# 2te8LED_v04.net
KiCad netlist of a schematic drawn in EAGLE
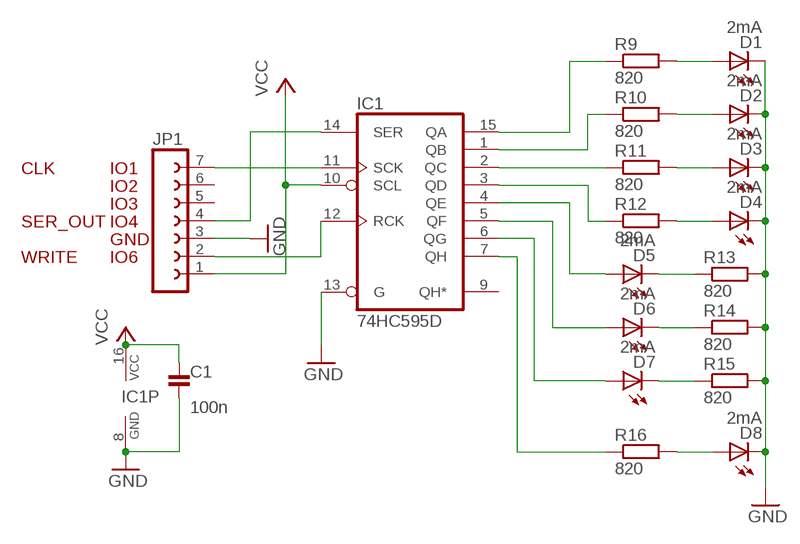
[diagram p0: schematic, sheet 1]

(export (version "E")
  (design (tool "Eeschema 10.0.6"))
  (components
    (comp (ref "C1")
      (value "100n")
      (footprint "eagle-import:C0805")
      (libsource (lib "eagle-import") (part "C-EUC0805"))
    )
    (comp (ref "D1")
      (value "2mA")
      (footprint "eagle-import:LED3MM")
      (libsource (lib "eagle-import") (part "LED3MM"))
    )
    (comp (ref "D2")
      (value "2mA")
      (footprint "eagle-import:LED3MM")
      (libsource (lib "eagle-import") (part "LED3MM"))
    )
    (comp (ref "D3")
      (value "2mA")
      (footprint "eagle-import:LED3MM")
      (libsource (lib "eagle-import") (part "LED3MM"))
    )
    (comp (ref "D4")
      (value "2mA")
      (footprint "eagle-import:LED3MM")
      (libsource (lib "eagle-import") (part "LED3MM"))
    )
    (comp (ref "D5")
      (value "2mA")
      (footprint "eagle-import:LED3MM")
      (libsource (lib "eagle-import") (part "LED3MM"))
    )
    (comp (ref "D6")
      (value "2mA")
      (footprint "eagle-import:LED3MM")
      (libsource (lib "eagle-import") (part "LED3MM"))
    )
    (comp (ref "D7")
      (value "2mA")
      (footprint "eagle-import:LED3MM")
      (libsource (lib "eagle-import") (part "LED3MM"))
    )
    (comp (ref "D8")
      (value "2mA")
      (footprint "eagle-import:LED3MM")
      (libsource (lib "eagle-import") (part "LED3MM"))
    )
    (comp (ref "IC1")
      (value "74HC595D")
      (footprint "eagle-import:SO16")
      (libsource (lib "eagle-import") (part "74595DHC"))
    )
    (comp (ref "JP1")
      (value "FE07-1")
      (footprint "eagle-import:FE07")
      (libsource (lib "eagle-import") (part "FE07-1"))
    )
    (comp (ref "R9")
      (value "820")
      (footprint "eagle-import:R0805")
      (libsource (lib "eagle-import") (part "R-EU_R0805"))
    )
    (comp (ref "R10")
      (value "820")
      (footprint "eagle-import:R0805")
      (libsource (lib "eagle-import") (part "R-EU_R0805"))
    )
    (comp (ref "R11")
      (value "820")
      (footprint "eagle-import:R0805")
      (libsource (lib "eagle-import") (part "R-EU_R0805"))
    )
    (comp (ref "R12")
      (value "820")
      (footprint "eagle-import:R0805")
      (libsource (lib "eagle-import") (part "R-EU_R0805"))
    )
    (comp (ref "R13")
      (value "820")
      (footprint "eagle-import:R0805")
      (libsource (lib "eagle-import") (part "R-EU_R0805"))
    )
    (comp (ref "R14")
      (value "820")
      (footprint "eagle-import:R0805")
      (libsource (lib "eagle-import") (part "R-EU_R0805"))
    )
    (comp (ref "R15")
      (value "820")
      (footprint "eagle-import:R0805")
      (libsource (lib "eagle-import") (part "R-EU_R0805"))
    )
    (comp (ref "R16")
      (value "820")
      (footprint "eagle-import:R0805")
      (libsource (lib "eagle-import") (part "R-EU_R0805"))
    )
  )
  (nets
    (net (code "1") (name "GND") (class "Default")
      (node (ref "C1") (pin "2") (pinfunction "2_2") (pintype "passive"))
      (node (ref "D1") (pin "K") (pinfunction "C_K") (pintype "passive"))
      (node (ref "D2") (pin "K") (pinfunction "C_K") (pintype "passive"))
      (node (ref "D3") (pin "K") (pinfunction "C_K") (pintype "passive"))
      (node (ref "D4") (pin "K") (pinfunction "C_K") (pintype "passive"))
      (node (ref "D8") (pin "K") (pinfunction "C_K") (pintype "passive"))
      (node (ref "IC1") (pin "13") (pinfunction "G_13") (pintype "input"))
      (node (ref "IC1") (pin "8") (pinfunction "GND_8") (pintype "power_in"))
      (node (ref "JP1") (pin "3") (pinfunction "3_3") (pintype "passive"))
      (node (ref "R13") (pin "2") (pinfunction "2_2") (pintype "passive"))
      (node (ref "R14") (pin "2") (pinfunction "2_2") (pintype "passive"))
      (node (ref "R15") (pin "2") (pinfunction "2_2") (pintype "passive"))
    )
    (net (code "2") (name "Net-(D1-PadA)") (class "Default")
      (node (ref "D1") (pin "A") (pinfunction "A_A") (pintype "passive"))
      (node (ref "R9") (pin "2") (pinfunction "2_2") (pintype "passive"))
    )
    (net (code "3") (name "Net-(D2-PadA)") (class "Default")
      (node (ref "D2") (pin "A") (pinfunction "A_A") (pintype "passive"))
      (node (ref "R10") (pin "2") (pinfunction "2_2") (pintype "passive"))
    )
    (net (code "4") (name "Net-(D3-PadA)") (class "Default")
      (node (ref "D3") (pin "A") (pinfunction "A_A") (pintype "passive"))
      (node (ref "R11") (pin "2") (pinfunction "2_2") (pintype "passive"))
    )
    (net (code "5") (name "Net-(D4-PadA)") (class "Default")
      (node (ref "D4") (pin "A") (pinfunction "A_A") (pintype "passive"))
      (node (ref "R12") (pin "2") (pinfunction "2_2") (pintype "passive"))
    )
    (net (code "6") (name "Net-(D5-C)") (class "Default")
      (node (ref "D5") (pin "K") (pinfunction "C_K") (pintype "passive"))
      (node (ref "R13") (pin "1") (pinfunction "1_1") (pintype "passive"))
    )
    (net (code "7") (name "Net-(D6-C)") (class "Default")
      (node (ref "D6") (pin "K") (pinfunction "C_K") (pintype "passive"))
      (node (ref "R14") (pin "1") (pinfunction "1_1") (pintype "passive"))
    )
    (net (code "8") (name "Net-(D7-C)") (class "Default")
      (node (ref "D7") (pin "K") (pinfunction "C_K") (pintype "passive"))
      (node (ref "R15") (pin "1") (pinfunction "1_1") (pintype "passive"))
    )
    (net (code "9") (name "Net-(D8-PadA)") (class "Default")
      (node (ref "D8") (pin "A") (pinfunction "A_A") (pintype "passive"))
      (node (ref "R16") (pin "2") (pinfunction "2_2") (pintype "passive"))
    )
    (net (code "10") (name "Net-(IC1A-QA)") (class "Default")
      (node (ref "IC1") (pin "15") (pinfunction "QA_15") (pintype "tri_state"))
      (node (ref "R9") (pin "1") (pinfunction "1_1") (pintype "passive"))
    )
    (net (code "11") (name "Net-(IC1A-QB)") (class "Default")
      (node (ref "IC1") (pin "1") (pinfunction "QB_1") (pintype "tri_state"))
      (node (ref "R10") (pin "1") (pinfunction "1_1") (pintype "passive"))
    )
    (net (code "12") (name "Net-(IC1A-QC)") (class "Default")
      (node (ref "IC1") (pin "2") (pinfunction "QC_2") (pintype "tri_state"))
      (node (ref "R11") (pin "1") (pinfunction "1_1") (pintype "passive"))
    )
    (net (code "13") (name "Net-(IC1A-QD)") (class "Default")
      (node (ref "IC1") (pin "3") (pinfunction "QD_3") (pintype "tri_state"))
      (node (ref "R12") (pin "1") (pinfunction "1_1") (pintype "passive"))
    )
    (net (code "14") (name "Net-(IC1A-QE)") (class "Default")
      (node (ref "D5") (pin "A") (pinfunction "A_A") (pintype "passive"))
      (node (ref "IC1") (pin "4") (pinfunction "QE_4") (pintype "tri_state"))
    )
    (net (code "15") (name "Net-(IC1A-QF)") (class "Default")
      (node (ref "D6") (pin "A") (pinfunction "A_A") (pintype "passive"))
      (node (ref "IC1") (pin "5") (pinfunction "QF_5") (pintype "tri_state"))
    )
    (net (code "16") (name "Net-(IC1A-QG)") (class "Default")
      (node (ref "D7") (pin "A") (pinfunction "A_A") (pintype "passive"))
      (node (ref "IC1") (pin "6") (pinfunction "QG_6") (pintype "tri_state"))
    )
    (net (code "17") (name "Net-(IC1A-QH)") (class "Default")
      (node (ref "IC1") (pin "7") (pinfunction "QH_7") (pintype "tri_state"))
      (node (ref "R16") (pin "1") (pinfunction "1_1") (pintype "passive"))
    )
    (net (code "18") (name "Net-(IC1A-RCK)") (class "Default")
      (node (ref "IC1") (pin "12") (pinfunction "RCK_12") (pintype "input"))
      (node (ref "JP1") (pin "2") (pinfunction "2_2") (pintype "passive"))
    )
    (net (code "19") (name "Net-(IC1A-SCK)") (class "Default")
      (node (ref "IC1") (pin "11") (pinfunction "SCK_11") (pintype "input"))
      (node (ref "JP1") (pin "7") (pinfunction "7_7") (pintype "passive"))
    )
    (net (code "20") (name "Net-(IC1A-SER)") (class "Default")
      (node (ref "IC1") (pin "14") (pinfunction "SER_14") (pintype "input"))
      (node (ref "JP1") (pin "4") (pinfunction "4_4") (pintype "passive"))
    )
    (net (code "21") (name "VCC") (class "Default")
      (node (ref "C1") (pin "1") (pinfunction "1_1") (pintype "passive"))
      (node (ref "IC1") (pin "10") (pinfunction "SCL_10") (pintype "input"))
      (node (ref "IC1") (pin "16") (pinfunction "VCC_16") (pintype "power_in"))
      (node (ref "JP1") (pin "1") (pinfunction "1_1") (pintype "passive"))
    )
    (net (code "22") (name "unconnected-(IC1A-QH*-Pad9)") (class "Default")
      (node (ref "IC1") (pin "9") (pinfunction "QH*_9") (pintype "tri_state"))
    )
    (net (code "23") (name "unconnected-(JP1-Pad5)") (class "Default")
      (node (ref "JP1") (pin "5") (pinfunction "5_5") (pintype "passive"))
    )
    (net (code "24") (name "unconnected-(JP1-Pad6)") (class "Default")
      (node (ref "JP1") (pin "6") (pinfunction "6_6") (pintype "passive"))
    )
  )
)
